# Periphery.net
KiCad netlist of a schematic drawn in Altium Designer
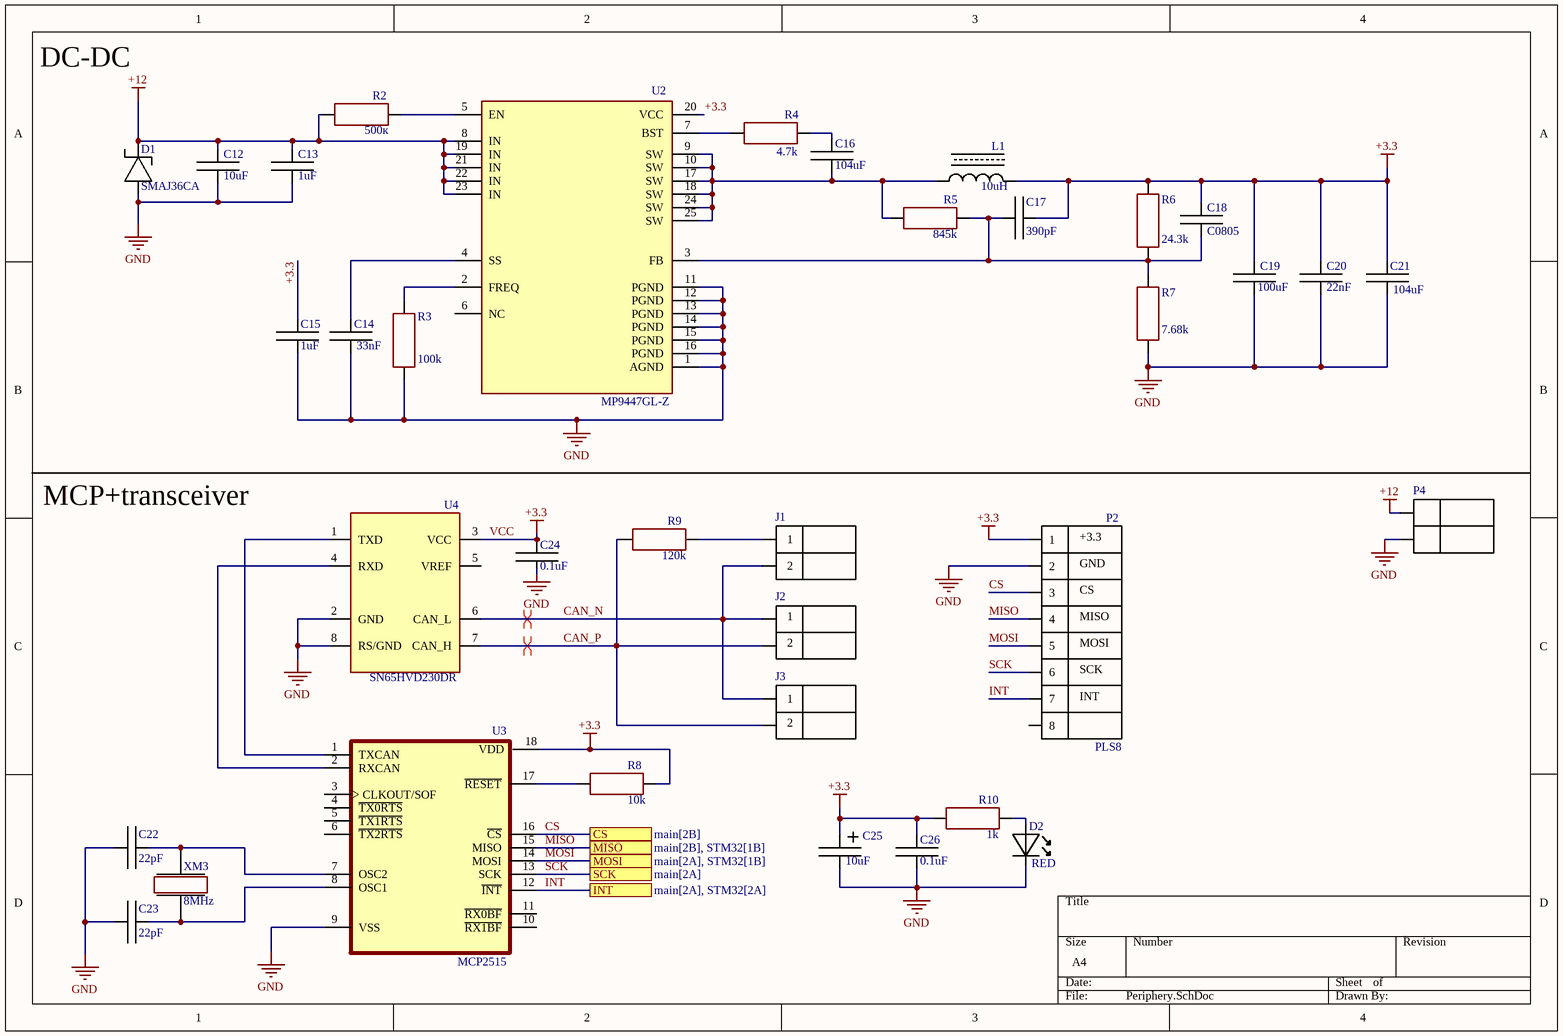
[diagram p0: Periphery.SchDoc]

(export (version "E")
  (design (tool "Eeschema 10.0.6"))
  (components
    (comp (ref "C12")
      (value "10uF")
      (footprint "C0805")
      (description "Керамический конденсатор. 1uF,10uF,106uF,33pF,100uF")
      (libsource (lib "Integrated_Library1") (part "C0805"))
    )
    (comp (ref "C13")
      (value "1uF")
      (footprint "C0805")
      (description "Керамический конденсатор. 1uF,10uF,106uF,33pF,100uF")
      (libsource (lib "Integrated_Library1") (part "C0805"))
    )
    (comp (ref "C15")
      (value "1uF")
      (footprint "C0805")
      (description "Керамический конденсатор. 1uF,10uF,106uF,33pF,100uF")
      (libsource (lib "Integrated_Library1") (part "C0805"))
    )
    (comp (ref "C16")
      (value "104uF")
      (footprint "C0805")
      (description "Керамический конденсатор. 1uF,10uF,106uF,33pF,100uF")
      (libsource (lib "Integrated_Library1") (part "C0805"))
    )
    (comp (ref "C17")
      (value "390pF")
      (footprint "C0805")
      (description "Керамический конденсатор. 1uF,10uF,106uF,33pF,100uF")
      (libsource (lib "Integrated_Library1") (part "C0805"))
    )
    (comp (ref "C18")
      (value "C0805")
      (footprint "C0805")
      (description "Керамический конденсатор. 1uF,10uF,106uF,33pF,100uF")
      (libsource (lib "Integrated_Library1") (part "C0805"))
    )
    (comp (ref "C19")
      (value "100uF")
      (footprint "C0805")
      (description "Керамический конденсатор. 1uF,10uF,106uF,33pF,100uF")
      (libsource (lib "Integrated_Library1") (part "C0805"))
    )
    (comp (ref "C20")
      (value "22nF")
      (footprint "C0805")
      (description "Керамический конденсатор. 1uF,10uF,106uF,33pF,100uF")
      (libsource (lib "") (part "C0805_1"))
    )
    (comp (ref "C21")
      (value "104uF")
      (footprint "C0805")
      (description "Керамический конденсатор. 1uF,10uF,106uF,33pF,100uF")
      (libsource (lib "Integrated_Library1") (part "C0805"))
    )
    (comp (ref "C22")
      (value "22pF")
      (footprint "C0805")
      (description "Керамический конденсатор. 1uF,10uF,106uF,33pF,100uF")
      (libsource (lib "Integrated_Library1") (part "C0805"))
    )
    (comp (ref "C23")
      (value "22pF")
      (footprint "C0805")
      (description "Керамический конденсатор. 1uF,10uF,106uF,33pF,100uF")
      (libsource (lib "Integrated_Library1") (part "C0805"))
    )
    (comp (ref "C24")
      (value "0.1uF")
      (footprint "C0805")
      (description "Керамический конденсатор. 1uF,10uF,106uF,33pF,100uF")
      (libsource (lib "Integrated_Library1") (part "C0805"))
    )
    (comp (ref "C25")
      (value "10uF")
      (footprint "CAP_3.5 (8x12мм)")
      (description "Электролит конденсатор (8x12мм)")
      (libsource (lib "Integrated_Library1") (part "C_3.5"))
    )
    (comp (ref "C26")
      (value "0.1uF")
      (footprint "C0805")
      (description "Керамический конденсатор. 1uF,10uF,106uF,33pF,100uF")
      (libsource (lib "Integrated_Library1") (part "C0805"))
    )
    (comp (ref "D1")
      (value "SMAJ36CA")
      (footprint "SMAJ36CA")
      (libsource (lib "Integrated_Library1") (part "SMAJ36CA"))
    )
    (comp (ref "D2")
      (value "RED")
      (footprint "LED0805")
      (description "SMD 0805")
      (libsource (lib "Integrated_Library1") (part "Led"))
    )
    (comp (ref "J1") (value "PLS2") (footprint "PLS2") (libsource (lib "Integrated_Library2") (part "PLS2")))
    (comp (ref "J2") (value "PLS2") (footprint "PLS2") (libsource (lib "Integrated_Library2") (part "PLS2")))
    (comp (ref "J3") (value "PLS2") (footprint "PLS2") (libsource (lib "Integrated_Library2") (part "PLS2")))
    (comp (ref "L1")
      (value "10uH")
      (footprint "Inductor 10uH 8A")
      (libsource (lib "Integrated_Library1") (part "Inductor SMD"))
    )
    (comp (ref "P2") (value "PLS8") (footprint "PLS8") (libsource (lib "Integrated_Library1") (part "PLS8")))
    (comp (ref "P4") (value "PLS2") (footprint "PLS2") (libsource (lib "Integrated_Library2") (part "PLS2")))
    (comp (ref "R2")
      (value "500к")
      (footprint "R0805")
      (description "SMD")
      (libsource (lib "Integrated_Library1") (part "R0805"))
    )
    (comp (ref "R3")
      (value "100k")
      (footprint "R0805")
      (description "SMD")
      (libsource (lib "") (part "R0805_1"))
    )
    (comp (ref "R4")
      (value "4.7k")
      (footprint "R0805")
      (description "SMD")
      (libsource (lib "Integrated_Library1") (part "R0805"))
    )
    (comp (ref "R5")
      (value "845k")
      (footprint "R0805")
      (description "SMD")
      (libsource (lib "Integrated_Library1") (part "R0805"))
    )
    (comp (ref "R6")
      (value "24.3k")
      (footprint "R0805")
      (description "SMD")
      (libsource (lib "") (part "R0805_1"))
    )
    (comp (ref "R7")
      (value "7.68k")
      (footprint "R0805")
      (description "SMD")
      (libsource (lib "") (part "R0805_1"))
    )
    (comp (ref "R8")
      (value "10k")
      (footprint "R0805")
      (description "SMD")
      (libsource (lib "Integrated_Library1") (part "R0805"))
    )
    (comp (ref "R9")
      (value "120k")
      (footprint "R0805")
      (description "SMD")
      (libsource (lib "Integrated_Library1") (part "R0805"))
    )
    (comp (ref "R10")
      (value "1k")
      (footprint "R0805")
      (description "SMD")
      (libsource (lib "Integrated_Library1") (part "R0805"))
    )
    (comp (ref "U2")
      (value "MP9447GL-Z")
      (footprint "MP9447GL-Z")
      (libsource (lib "Integrated_Library1") (part "MP9447GL-Z"))
    )
    (comp (ref "U3")
      (value "MCP2515")
      (footprint "MCP2515")
      (description "MCP2515-I/SO")
      (libsource (lib "Integrated_Library1") (part "MCP2515"))
    )
    (comp (ref "U4")
      (value "SN65HVD230DR")
      (footprint "SN65HVD230DR")
      (description "трансивер, 1Мбит/с, 3-3,6ВDC, SO8")
      (libsource (lib "Integrated_Library1") (part "SN65HVD230DR"))
    )
    (comp (ref "XM3")
      (value "8MHz")
      (footprint "Resonator")
      (libsource (lib "Integrated_Library1") (part "Resonator"))
    )
    (comp (ref "С14")
      (value "33nF")
      (footprint "C0805")
      (description "Керамический конденсатор. 1uF,10uF,106uF,33pF,100uF")
      (libsource (lib "Integrated_Library1") (part "C0805"))
    )
  )
  (nets
    (net (code "1") (name "+3.3") (class "Default")
      (node (ref "C15") (pin "2") (pinfunction "2_2") (pintype "passive"))
      (node (ref "C17") (pin "2") (pinfunction "2_2") (pintype "passive"))
      (node (ref "C18") (pin "2") (pinfunction "2_2") (pintype "passive"))
      (node (ref "C19") (pin "2") (pinfunction "2_2") (pintype "passive"))
      (node (ref "C20") (pin "2") (pinfunction "2_2") (pintype "passive"))
      (node (ref "C21") (pin "2") (pinfunction "2_2") (pintype "passive"))
      (node (ref "C24") (pin "2") (pinfunction "2_2") (pintype "passive"))
      (node (ref "C25") (pin "1") (pinfunction "1_1") (pintype "passive"))
      (node (ref "C26") (pin "2") (pinfunction "2_2") (pintype "passive"))
      (node (ref "L1") (pin "1") (pinfunction "1_1") (pintype "passive"))
      (node (ref "P2") (pin "1") (pinfunction "1_1") (pintype "passive"))
      (node (ref "R10") (pin "1") (pinfunction "1_1") (pintype "passive"))
      (node (ref "R6") (pin "2") (pinfunction "2_2") (pintype "passive"))
      (node (ref "R8") (pin "2") (pinfunction "2_2") (pintype "passive"))
      (node (ref "U2") (pin "20") (pinfunction "VCC_20") (pintype "passive"))
      (node (ref "U3") (pin "18") (pinfunction "VDD_18") (pintype "passive"))
      (node (ref "U4") (pin "3") (pinfunction "VCC_3") (pintype "passive"))
    )
    (net (code "2") (name "+12") (class "Default")
      (node (ref "C12") (pin "2") (pinfunction "2_2") (pintype "passive"))
      (node (ref "C13") (pin "2") (pinfunction "2_2") (pintype "passive"))
      (node (ref "D1") (pin "2") (pinfunction "2_2") (pintype "passive"))
      (node (ref "P4") (pin "2") (pinfunction "2_2") (pintype "passive"))
      (node (ref "R2") (pin "1") (pinfunction "1_1") (pintype "passive"))
      (node (ref "U2") (pin "19") (pinfunction "IN_19") (pintype "passive"))
      (node (ref "U2") (pin "21") (pinfunction "IN_21") (pintype "passive"))
      (node (ref "U2") (pin "22") (pinfunction "IN_22") (pintype "passive"))
      (node (ref "U2") (pin "23") (pinfunction "IN_23") (pintype "passive"))
      (node (ref "U2") (pin "8") (pinfunction "IN_8") (pintype "passive"))
    )
    (net (code "3") (name "/CAN_N") (class "Default")
      (node (ref "J1") (pin "1") (pinfunction "1_1") (pintype "passive"))
      (node (ref "J2") (pin "2") (pinfunction "2_2") (pintype "passive"))
      (node (ref "J3") (pin "2") (pinfunction "2_2") (pintype "passive"))
      (node (ref "U4") (pin "6") (pinfunction "CAN_L_6") (pintype "passive"))
    )
    (net (code "4") (name "/CAN_P") (class "Default")
      (node (ref "J2") (pin "1") (pinfunction "1_1") (pintype "passive"))
      (node (ref "J3") (pin "1") (pinfunction "1_1") (pintype "passive"))
      (node (ref "R9") (pin "1") (pinfunction "1_1") (pintype "passive"))
      (node (ref "U4") (pin "7") (pinfunction "CAN_H_7") (pintype "passive"))
    )
    (net (code "5") (name "/CS") (class "Default")
      (node (ref "P2") (pin "3") (pinfunction "3_3") (pintype "passive"))
      (node (ref "U3") (pin "16") (pinfunction "~{CS}_16") (pintype "passive"))
    )
    (net (code "6") (name "/INT") (class "Default")
      (node (ref "P2") (pin "7") (pinfunction "7_7") (pintype "passive"))
      (node (ref "U3") (pin "12") (pinfunction "~{INT}_12") (pintype "passive"))
    )
    (net (code "7") (name "/MISO") (class "Default")
      (node (ref "P2") (pin "4") (pinfunction "4_4") (pintype "passive"))
      (node (ref "U3") (pin "15") (pinfunction "MISO_15") (pintype "passive"))
    )
    (net (code "8") (name "/MOSI") (class "Default")
      (node (ref "P2") (pin "5") (pinfunction "5_5") (pintype "passive"))
      (node (ref "U3") (pin "14") (pinfunction "MOSI_14") (pintype "passive"))
    )
    (net (code "9") (name "/SCK") (class "Default")
      (node (ref "P2") (pin "6") (pinfunction "6_6") (pintype "passive"))
      (node (ref "U3") (pin "13") (pinfunction "SCK_13") (pintype "passive"))
    )
    (net (code "10") (name "GND") (class "Default")
      (node (ref "C12") (pin "1") (pinfunction "1_1") (pintype "passive"))
      (node (ref "C13") (pin "1") (pinfunction "1_1") (pintype "passive"))
      (node (ref "C15") (pin "1") (pinfunction "1_1") (pintype "passive"))
      (node (ref "C19") (pin "1") (pinfunction "1_1") (pintype "passive"))
      (node (ref "C20") (pin "1") (pinfunction "1_1") (pintype "passive"))
      (node (ref "C21") (pin "1") (pinfunction "1_1") (pintype "passive"))
      (node (ref "C22") (pin "1") (pinfunction "1_1") (pintype "passive"))
      (node (ref "C23") (pin "1") (pinfunction "1_1") (pintype "passive"))
      (node (ref "C24") (pin "1") (pinfunction "1_1") (pintype "passive"))
      (node (ref "C25") (pin "2") (pinfunction "2_2") (pintype "passive"))
      (node (ref "C26") (pin "1") (pinfunction "1_1") (pintype "passive"))
      (node (ref "D1") (pin "1") (pinfunction "1_1") (pintype "passive"))
      (node (ref "D2") (pin "C") (pinfunction "2_C") (pintype "passive"))
      (node (ref "P2") (pin "2") (pinfunction "2_2") (pintype "passive"))
      (node (ref "P4") (pin "1") (pinfunction "1_1") (pintype "passive"))
      (node (ref "R3") (pin "1") (pinfunction "1_1") (pintype "passive"))
      (node (ref "R7") (pin "1") (pinfunction "1_1") (pintype "passive"))
      (node (ref "U2") (pin "1") (pinfunction "AGND_1") (pintype "passive"))
      (node (ref "U2") (pin "11") (pinfunction "PGND_11") (pintype "passive"))
      (node (ref "U2") (pin "12") (pinfunction "PGND_12") (pintype "passive"))
      (node (ref "U2") (pin "13") (pinfunction "PGND_13") (pintype "passive"))
      (node (ref "U2") (pin "14") (pinfunction "PGND_14") (pintype "passive"))
      (node (ref "U2") (pin "15") (pinfunction "PGND_15") (pintype "passive"))
      (node (ref "U2") (pin "16") (pinfunction "PGND_16") (pintype "passive"))
      (node (ref "U3") (pin "9") (pinfunction "VSS_9") (pintype "passive"))
      (node (ref "U4") (pin "2") (pinfunction "GND_2") (pintype "passive"))
      (node (ref "U4") (pin "8") (pinfunction "RS/GND_8") (pintype "passive"))
      (node (ref "С14") (pin "1") (pinfunction "1_1") (pintype "passive"))
    )
    (net (code "11") (name "Net-(C16-Pad1)") (class "Default")
      (node (ref "C16") (pin "1") (pinfunction "1_1") (pintype "passive"))
      (node (ref "L1") (pin "2") (pinfunction "2_2") (pintype "passive"))
      (node (ref "R5") (pin "1") (pinfunction "1_1") (pintype "passive"))
      (node (ref "U2") (pin "10") (pinfunction "SW_10") (pintype "passive"))
      (node (ref "U2") (pin "17") (pinfunction "SW_17") (pintype "passive"))
      (node (ref "U2") (pin "18") (pinfunction "SW_18") (pintype "passive"))
      (node (ref "U2") (pin "24") (pinfunction "SW_24") (pintype "passive"))
      (node (ref "U2") (pin "25") (pinfunction "SW_25") (pintype "passive"))
      (node (ref "U2") (pin "9") (pinfunction "SW_9") (pintype "passive"))
    )
    (net (code "12") (name "Net-(C16-Pad2)") (class "Default")
      (node (ref "C16") (pin "2") (pinfunction "2_2") (pintype "passive"))
      (node (ref "R4") (pin "2") (pinfunction "2_2") (pintype "passive"))
    )
    (net (code "13") (name "Net-(D2-1)") (class "Default")
      (node (ref "D2") (pin "A") (pinfunction "1_A") (pintype "passive"))
      (node (ref "R10") (pin "2") (pinfunction "2_2") (pintype "passive"))
    )
    (net (code "14") (name "Net-(J1-Pad2)") (class "Default")
      (node (ref "J1") (pin "2") (pinfunction "2_2") (pintype "passive"))
      (node (ref "R9") (pin "2") (pinfunction "2_2") (pintype "passive"))
    )
    (net (code "15") (name "Net-(U2-BST)") (class "Default")
      (node (ref "R4") (pin "1") (pinfunction "1_1") (pintype "passive"))
      (node (ref "U2") (pin "7") (pinfunction "BST_7") (pintype "passive"))
    )
    (net (code "16") (name "Net-(U2-EN)") (class "Default")
      (node (ref "R2") (pin "2") (pinfunction "2_2") (pintype "passive"))
      (node (ref "U2") (pin "5") (pinfunction "EN_5") (pintype "passive"))
    )
    (net (code "17") (name "Net-(U2-FB)") (class "Default")
      (node (ref "C17") (pin "1") (pinfunction "1_1") (pintype "passive"))
      (node (ref "C18") (pin "1") (pinfunction "1_1") (pintype "passive"))
      (node (ref "R5") (pin "2") (pinfunction "2_2") (pintype "passive"))
      (node (ref "R6") (pin "1") (pinfunction "1_1") (pintype "passive"))
      (node (ref "R7") (pin "2") (pinfunction "2_2") (pintype "passive"))
      (node (ref "U2") (pin "3") (pinfunction "FB_3") (pintype "passive"))
    )
    (net (code "18") (name "Net-(U2-FREQ)") (class "Default")
      (node (ref "R3") (pin "2") (pinfunction "2_2") (pintype "passive"))
      (node (ref "U2") (pin "2") (pinfunction "FREQ_2") (pintype "passive"))
    )
    (net (code "19") (name "Net-(U2-SS)") (class "Default")
      (node (ref "U2") (pin "4") (pinfunction "SS_4") (pintype "passive"))
      (node (ref "С14") (pin "2") (pinfunction "2_2") (pintype "passive"))
    )
    (net (code "20") (name "Net-(U3-OSC1)") (class "Default")
      (node (ref "C23") (pin "2") (pinfunction "2_2") (pintype "passive"))
      (node (ref "U3") (pin "8") (pinfunction "OSC1_8") (pintype "passive"))
      (node (ref "XM3") (pin "1") (pinfunction "1_1") (pintype "passive"))
    )
    (net (code "21") (name "Net-(U3-OSC2)") (class "Default")
      (node (ref "C22") (pin "2") (pinfunction "2_2") (pintype "passive"))
      (node (ref "U3") (pin "7") (pinfunction "OSC2_7") (pintype "passive"))
      (node (ref "XM3") (pin "2") (pinfunction "2_2") (pintype "passive"))
    )
    (net (code "22") (name "Net-(U3-RXCAN)") (class "Default")
      (node (ref "U3") (pin "2") (pinfunction "RXCAN_2") (pintype "passive"))
      (node (ref "U4") (pin "4") (pinfunction "RXD_4") (pintype "passive"))
    )
    (net (code "23") (name "Net-(U3-TXCAN)") (class "Default")
      (node (ref "U3") (pin "1") (pinfunction "TXCAN_1") (pintype "passive"))
      (node (ref "U4") (pin "1") (pinfunction "TXD_1") (pintype "passive"))
    )
    (net (code "24") (name "Net-(U3-~{RESET})") (class "Default")
      (node (ref "R8") (pin "1") (pinfunction "1_1") (pintype "passive"))
      (node (ref "U3") (pin "17") (pinfunction "~{RESET}_17") (pintype "passive"))
    )
    (net (code "25") (name "unconnected-(P2-Pad8)") (class "Default")
      (node (ref "P2") (pin "8") (pinfunction "8_8") (pintype "passive"))
    )
    (net (code "26") (name "unconnected-(U2-NC-Pad6)") (class "Default")
      (node (ref "U2") (pin "6") (pinfunction "NC_6") (pintype "passive"))
    )
    (net (code "27") (name "unconnected-(U3-CLKOUT{slash}SOF-Pad3)") (class "Default")
      (node (ref "U3") (pin "3") (pinfunction "CLKOUT/SOF_3") (pintype "passive"))
    )
    (net (code "28") (name "unconnected-(U3-~{RX0BF}-Pad11)") (class "Default")
      (node (ref "U3") (pin "11") (pinfunction "~{RX0BF}_11") (pintype "passive"))
    )
    (net (code "29") (name "unconnected-(U3-~{RX1BF}-Pad10)") (class "Default")
      (node (ref "U3") (pin "10") (pinfunction "~{RX1BF}_10") (pintype "passive"))
    )
    (net (code "30") (name "unconnected-(U3-~{TX0RTS}-Pad4)") (class "Default")
      (node (ref "U3") (pin "4") (pinfunction "~{TX0RTS}_4") (pintype "passive"))
    )
    (net (code "31") (name "unconnected-(U3-~{TX1RTS}-Pad5)") (class "Default")
      (node (ref "U3") (pin "5") (pinfunction "~{TX1RTS}_5") (pintype "passive"))
    )
    (net (code "32") (name "unconnected-(U3-~{TX2RTS}-Pad6)") (class "Default")
      (node (ref "U3") (pin "6") (pinfunction "~{TX2RTS}_6") (pintype "passive"))
    )
    (net (code "33") (name "unconnected-(U4-VREF-Pad5)") (class "Default")
      (node (ref "U4") (pin "5") (pinfunction "VREF_5") (pintype "passive"))
    )
  )
)
